# FlightComputerBoard1.net
KiCad netlist of a schematic drawn in EAGLE
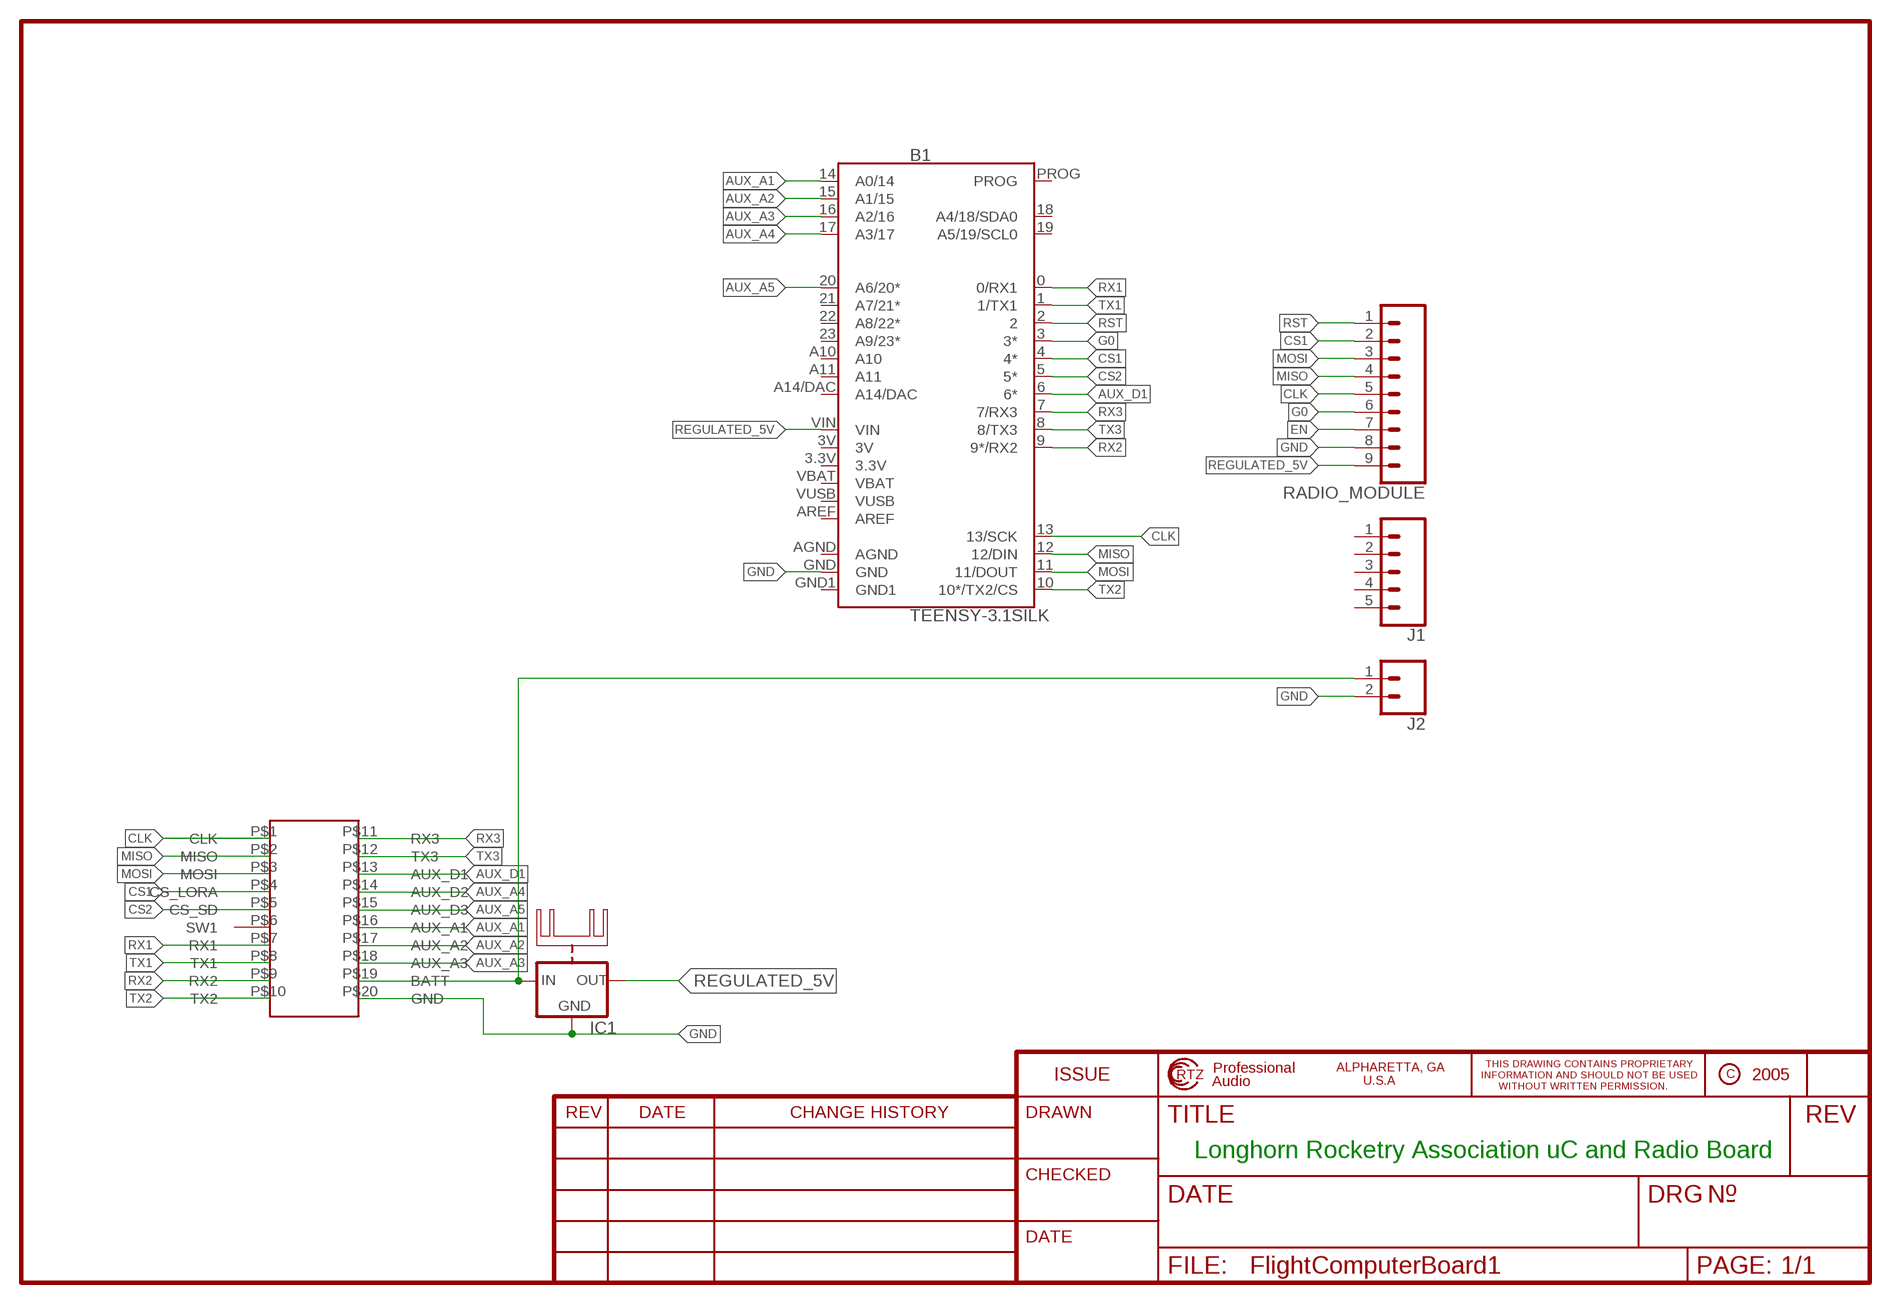
[diagram p0: schematic, sheet 1]

(export (version "E")
  (design (tool "Eeschema 10.0.6"))
  (components
    (comp (ref "B1")
      (value "TEENSY-3.1SILK")
      (footprint "eagle-import:TEENSY-3.1")
      (libsource (lib "eagle-import") (part "TEENSY-3.1SILK"))
    )
    (comp (ref "IC1")
      (value "78XXH")
      (footprint "eagle-import:78XXH")
      (libsource (lib "eagle-import") (part "78XXH"))
    )
    (comp (ref "J1")
      (value "CONN_05")
      (footprint "eagle-import:1X05")
      (libsource (lib "eagle-import") (part "CONN_05"))
    )
    (comp (ref "J2")
      (value "CONN_02")
      (footprint "eagle-import:1X02")
      (libsource (lib "eagle-import") (part "CONN_02"))
    )
    (comp (ref "RADIO_MODULE")
      (value "CONN_09")
      (footprint "eagle-import:1X09")
      (libsource (lib "eagle-import") (part "CONN_09"))
    )
    (comp (ref "U$1")
      (value "SMALLHEADERPACKAGE")
      (footprint "eagle-import:SMALLHEADERPACKAGE")
      (libsource (lib "eagle-import") (part "SMALLHEADERPACKAGE"))
    )
  )
  (nets
    (net (code "1") (name "/3.3V") (class "Default")
      (node (ref "B1") (pin "3.3V") (pinfunction "3.3V_3.3V") (pintype "power_in"))
    )
    (net (code "2") (name "/3V") (class "Default")
      (node (ref "B1") (pin "3V") (pinfunction "3V_3V") (pintype "power_in"))
    )
    (net (code "3") (name "/AGND") (class "Default")
      (node (ref "B1") (pin "AGND") (pinfunction "AGND_AGND") (pintype "power_in"))
    )
    (net (code "4") (name "/GND1") (class "Default")
      (node (ref "B1") (pin "GND1") (pinfunction "GND1_GND1") (pintype "power_in"))
    )
    (net (code "5") (name "/VBAT") (class "Default")
      (node (ref "B1") (pin "VBAT") (pinfunction "VBAT_VBAT") (pintype "power_in"))
    )
    (net (code "6") (name "/VUSB") (class "Default")
      (node (ref "B1") (pin "VUSB") (pinfunction "VUSB_VUSB") (pintype "power_in"))
    )
    (net (code "7") (name "AUX_A1") (class "Default")
      (node (ref "B1") (pin "14") (pinfunction "A0/14_14") (pintype "bidirectional"))
      (node (ref "U$1") (pin "P$16") (pinfunction "AUX_A1_P$16") (pintype "bidirectional"))
    )
    (net (code "8") (name "AUX_A2") (class "Default")
      (node (ref "B1") (pin "15") (pinfunction "A1/15_15") (pintype "bidirectional"))
      (node (ref "U$1") (pin "P$17") (pinfunction "AUX_A2_P$17") (pintype "bidirectional"))
    )
    (net (code "9") (name "AUX_A3") (class "Default")
      (node (ref "B1") (pin "16") (pinfunction "A2/16_16") (pintype "bidirectional"))
      (node (ref "U$1") (pin "P$18") (pinfunction "AUX_A3_P$18") (pintype "bidirectional"))
    )
    (net (code "10") (name "AUX_A4") (class "Default")
      (node (ref "B1") (pin "17") (pinfunction "A3/17_17") (pintype "bidirectional"))
      (node (ref "U$1") (pin "P$14") (pinfunction "AUX_D2_P$14") (pintype "bidirectional"))
    )
    (net (code "11") (name "AUX_A5") (class "Default")
      (node (ref "B1") (pin "20") (pinfunction "A6/20*_20") (pintype "bidirectional"))
      (node (ref "U$1") (pin "P$15") (pinfunction "AUX_D3_P$15") (pintype "bidirectional"))
    )
    (net (code "12") (name "AUX_D1") (class "Default")
      (node (ref "B1") (pin "6") (pinfunction "6*_6") (pintype "bidirectional"))
      (node (ref "U$1") (pin "P$13") (pinfunction "AUX_D1_P$13") (pintype "bidirectional"))
    )
    (net (code "13") (name "CLK") (class "Default")
      (node (ref "B1") (pin "13") (pinfunction "13/SCK_13") (pintype "bidirectional"))
      (node (ref "RADIO_MODULE") (pin "5") (pinfunction "5_5") (pintype "passive"))
      (node (ref "U$1") (pin "P$1") (pinfunction "CLK_P$1") (pintype "bidirectional"))
    )
    (net (code "14") (name "CS1") (class "Default")
      (node (ref "B1") (pin "4") (pinfunction "4*_4") (pintype "bidirectional"))
      (node (ref "RADIO_MODULE") (pin "2") (pinfunction "2_2") (pintype "passive"))
      (node (ref "U$1") (pin "P$4") (pinfunction "CS_LORA_P$4") (pintype "bidirectional"))
    )
    (net (code "15") (name "CS2") (class "Default")
      (node (ref "B1") (pin "5") (pinfunction "5*_5") (pintype "bidirectional"))
      (node (ref "U$1") (pin "P$5") (pinfunction "CS_SD_P$5") (pintype "bidirectional"))
    )
    (net (code "16") (name "EN") (class "Default")
      (node (ref "RADIO_MODULE") (pin "7") (pinfunction "7_7") (pintype "passive"))
    )
    (net (code "17") (name "G0") (class "Default")
      (node (ref "B1") (pin "3") (pinfunction "3*_3") (pintype "bidirectional"))
      (node (ref "RADIO_MODULE") (pin "6") (pinfunction "6_6") (pintype "passive"))
    )
    (net (code "18") (name "GND") (class "Default")
      (node (ref "B1") (pin "GND") (pinfunction "GND_GND") (pintype "power_in"))
      (node (ref "IC1") (pin "GND") (pinfunction "GND_GND") (pintype "input"))
      (node (ref "J2") (pin "2") (pinfunction "2_2") (pintype "passive"))
      (node (ref "RADIO_MODULE") (pin "8") (pinfunction "8_8") (pintype "passive"))
      (node (ref "U$1") (pin "P$20") (pinfunction "GND_P$20") (pintype "bidirectional"))
    )
    (net (code "19") (name "MISO") (class "Default")
      (node (ref "B1") (pin "12") (pinfunction "12/DIN_12") (pintype "bidirectional"))
      (node (ref "RADIO_MODULE") (pin "4") (pinfunction "4_4") (pintype "passive"))
      (node (ref "U$1") (pin "P$2") (pinfunction "MISO_P$2") (pintype "bidirectional"))
    )
    (net (code "20") (name "MOSI") (class "Default")
      (node (ref "B1") (pin "11") (pinfunction "11/DOUT_11") (pintype "bidirectional"))
      (node (ref "RADIO_MODULE") (pin "3") (pinfunction "3_3") (pintype "passive"))
      (node (ref "U$1") (pin "P$3") (pinfunction "MOSI_P$3") (pintype "bidirectional"))
    )
    (net (code "21") (name "Net-(U$1-BATT)") (class "Default")
      (node (ref "IC1") (pin "IN") (pinfunction "IN_IN") (pintype "input"))
      (node (ref "J2") (pin "1") (pinfunction "1_1") (pintype "passive"))
      (node (ref "U$1") (pin "P$19") (pinfunction "BATT_P$19") (pintype "bidirectional"))
    )
    (net (code "22") (name "REGULATED_5V") (class "Default")
      (node (ref "B1") (pin "VIN") (pinfunction "VIN_VIN") (pintype "power_in"))
      (node (ref "IC1") (pin "OUT") (pinfunction "OUT_OUT") (pintype "passive"))
      (node (ref "RADIO_MODULE") (pin "9") (pinfunction "9_9") (pintype "passive"))
    )
    (net (code "23") (name "RST") (class "Default")
      (node (ref "B1") (pin "2") (pinfunction "2_2") (pintype "bidirectional"))
      (node (ref "RADIO_MODULE") (pin "1") (pinfunction "1_1") (pintype "passive"))
    )
    (net (code "24") (name "RX1") (class "Default")
      (node (ref "B1") (pin "0") (pinfunction "0/RX1_0") (pintype "bidirectional"))
      (node (ref "U$1") (pin "P$7") (pinfunction "RX1_P$7") (pintype "bidirectional"))
    )
    (net (code "25") (name "RX2") (class "Default")
      (node (ref "B1") (pin "9") (pinfunction "9*/RX2_9") (pintype "bidirectional"))
      (node (ref "U$1") (pin "P$9") (pinfunction "RX2_P$9") (pintype "bidirectional"))
    )
    (net (code "26") (name "RX3") (class "Default")
      (node (ref "B1") (pin "7") (pinfunction "7/RX3_7") (pintype "bidirectional"))
      (node (ref "U$1") (pin "P$11") (pinfunction "RX3_P$11") (pintype "bidirectional"))
    )
    (net (code "27") (name "TX1") (class "Default")
      (node (ref "B1") (pin "1") (pinfunction "1/TX1_1") (pintype "bidirectional"))
      (node (ref "U$1") (pin "P$8") (pinfunction "TX1_P$8") (pintype "bidirectional"))
    )
    (net (code "28") (name "TX2") (class "Default")
      (node (ref "B1") (pin "10") (pinfunction "10*/TX2/CS_10") (pintype "bidirectional"))
      (node (ref "U$1") (pin "P$10") (pinfunction "TX2_P$10") (pintype "bidirectional"))
    )
    (net (code "29") (name "TX3") (class "Default")
      (node (ref "B1") (pin "8") (pinfunction "8/TX3_8") (pintype "bidirectional"))
      (node (ref "U$1") (pin "P$12") (pinfunction "TX3_P$12") (pintype "bidirectional"))
    )
    (net (code "30") (name "unconnected-(B1-A4{slash}18{slash}SDA0-Pad18)") (class "Default")
      (node (ref "B1") (pin "18") (pinfunction "A4/18/SDA0_18") (pintype "bidirectional"))
    )
    (net (code "31") (name "unconnected-(B1-A5{slash}19{slash}SCL0-Pad19)") (class "Default")
      (node (ref "B1") (pin "19") (pinfunction "A5/19/SCL0_19") (pintype "bidirectional"))
    )
    (net (code "32") (name "unconnected-(B1-A7{slash}21*-Pad21)") (class "Default")
      (node (ref "B1") (pin "21") (pinfunction "A7/21*_21") (pintype "bidirectional"))
    )
    (net (code "33") (name "unconnected-(B1-A8{slash}22*-Pad22)") (class "Default")
      (node (ref "B1") (pin "22") (pinfunction "A8/22*_22") (pintype "bidirectional"))
    )
    (net (code "34") (name "unconnected-(B1-A9{slash}23*-Pad23)") (class "Default")
      (node (ref "B1") (pin "23") (pinfunction "A9/23*_23") (pintype "bidirectional"))
    )
    (net (code "35") (name "unconnected-(B1-PadA10)") (class "Default")
      (node (ref "B1") (pin "A10") (pinfunction "A10_A10") (pintype "bidirectional"))
    )
    (net (code "36") (name "unconnected-(B1-PadA11)") (class "Default")
      (node (ref "B1") (pin "A11") (pinfunction "A11_A11") (pintype "bidirectional"))
    )
    (net (code "37") (name "unconnected-(B1-PadA14{slash}DAC)") (class "Default")
      (node (ref "B1") (pin "A14/DAC") (pinfunction "A14/DAC_A14/DAC") (pintype "bidirectional"))
    )
    (net (code "38") (name "unconnected-(B1-PadAREF)") (class "Default")
      (node (ref "B1") (pin "AREF") (pinfunction "AREF_AREF") (pintype "bidirectional"))
    )
    (net (code "39") (name "unconnected-(B1-PadPROG)") (class "Default")
      (node (ref "B1") (pin "PROG") (pinfunction "PROG_PROG") (pintype "bidirectional"))
    )
    (net (code "40") (name "unconnected-(J1-Pad1)") (class "Default")
      (node (ref "J1") (pin "1") (pinfunction "1_1") (pintype "passive"))
    )
    (net (code "41") (name "unconnected-(J1-Pad2)") (class "Default")
      (node (ref "J1") (pin "2") (pinfunction "2_2") (pintype "passive"))
    )
    (net (code "42") (name "unconnected-(J1-Pad3)") (class "Default")
      (node (ref "J1") (pin "3") (pinfunction "3_3") (pintype "passive"))
    )
    (net (code "43") (name "unconnected-(J1-Pad4)") (class "Default")
      (node (ref "J1") (pin "4") (pinfunction "4_4") (pintype "passive"))
    )
    (net (code "44") (name "unconnected-(J1-Pad5)") (class "Default")
      (node (ref "J1") (pin "5") (pinfunction "5_5") (pintype "passive"))
    )
    (net (code "45") (name "unconnected-(U$1-SW1-PadP$6)") (class "Default")
      (node (ref "U$1") (pin "P$6") (pinfunction "SW1_P$6") (pintype "bidirectional"))
    )
  )
)
